# 13_Periphs.net
KiCad netlist of a schematic drawn in Altium Designer
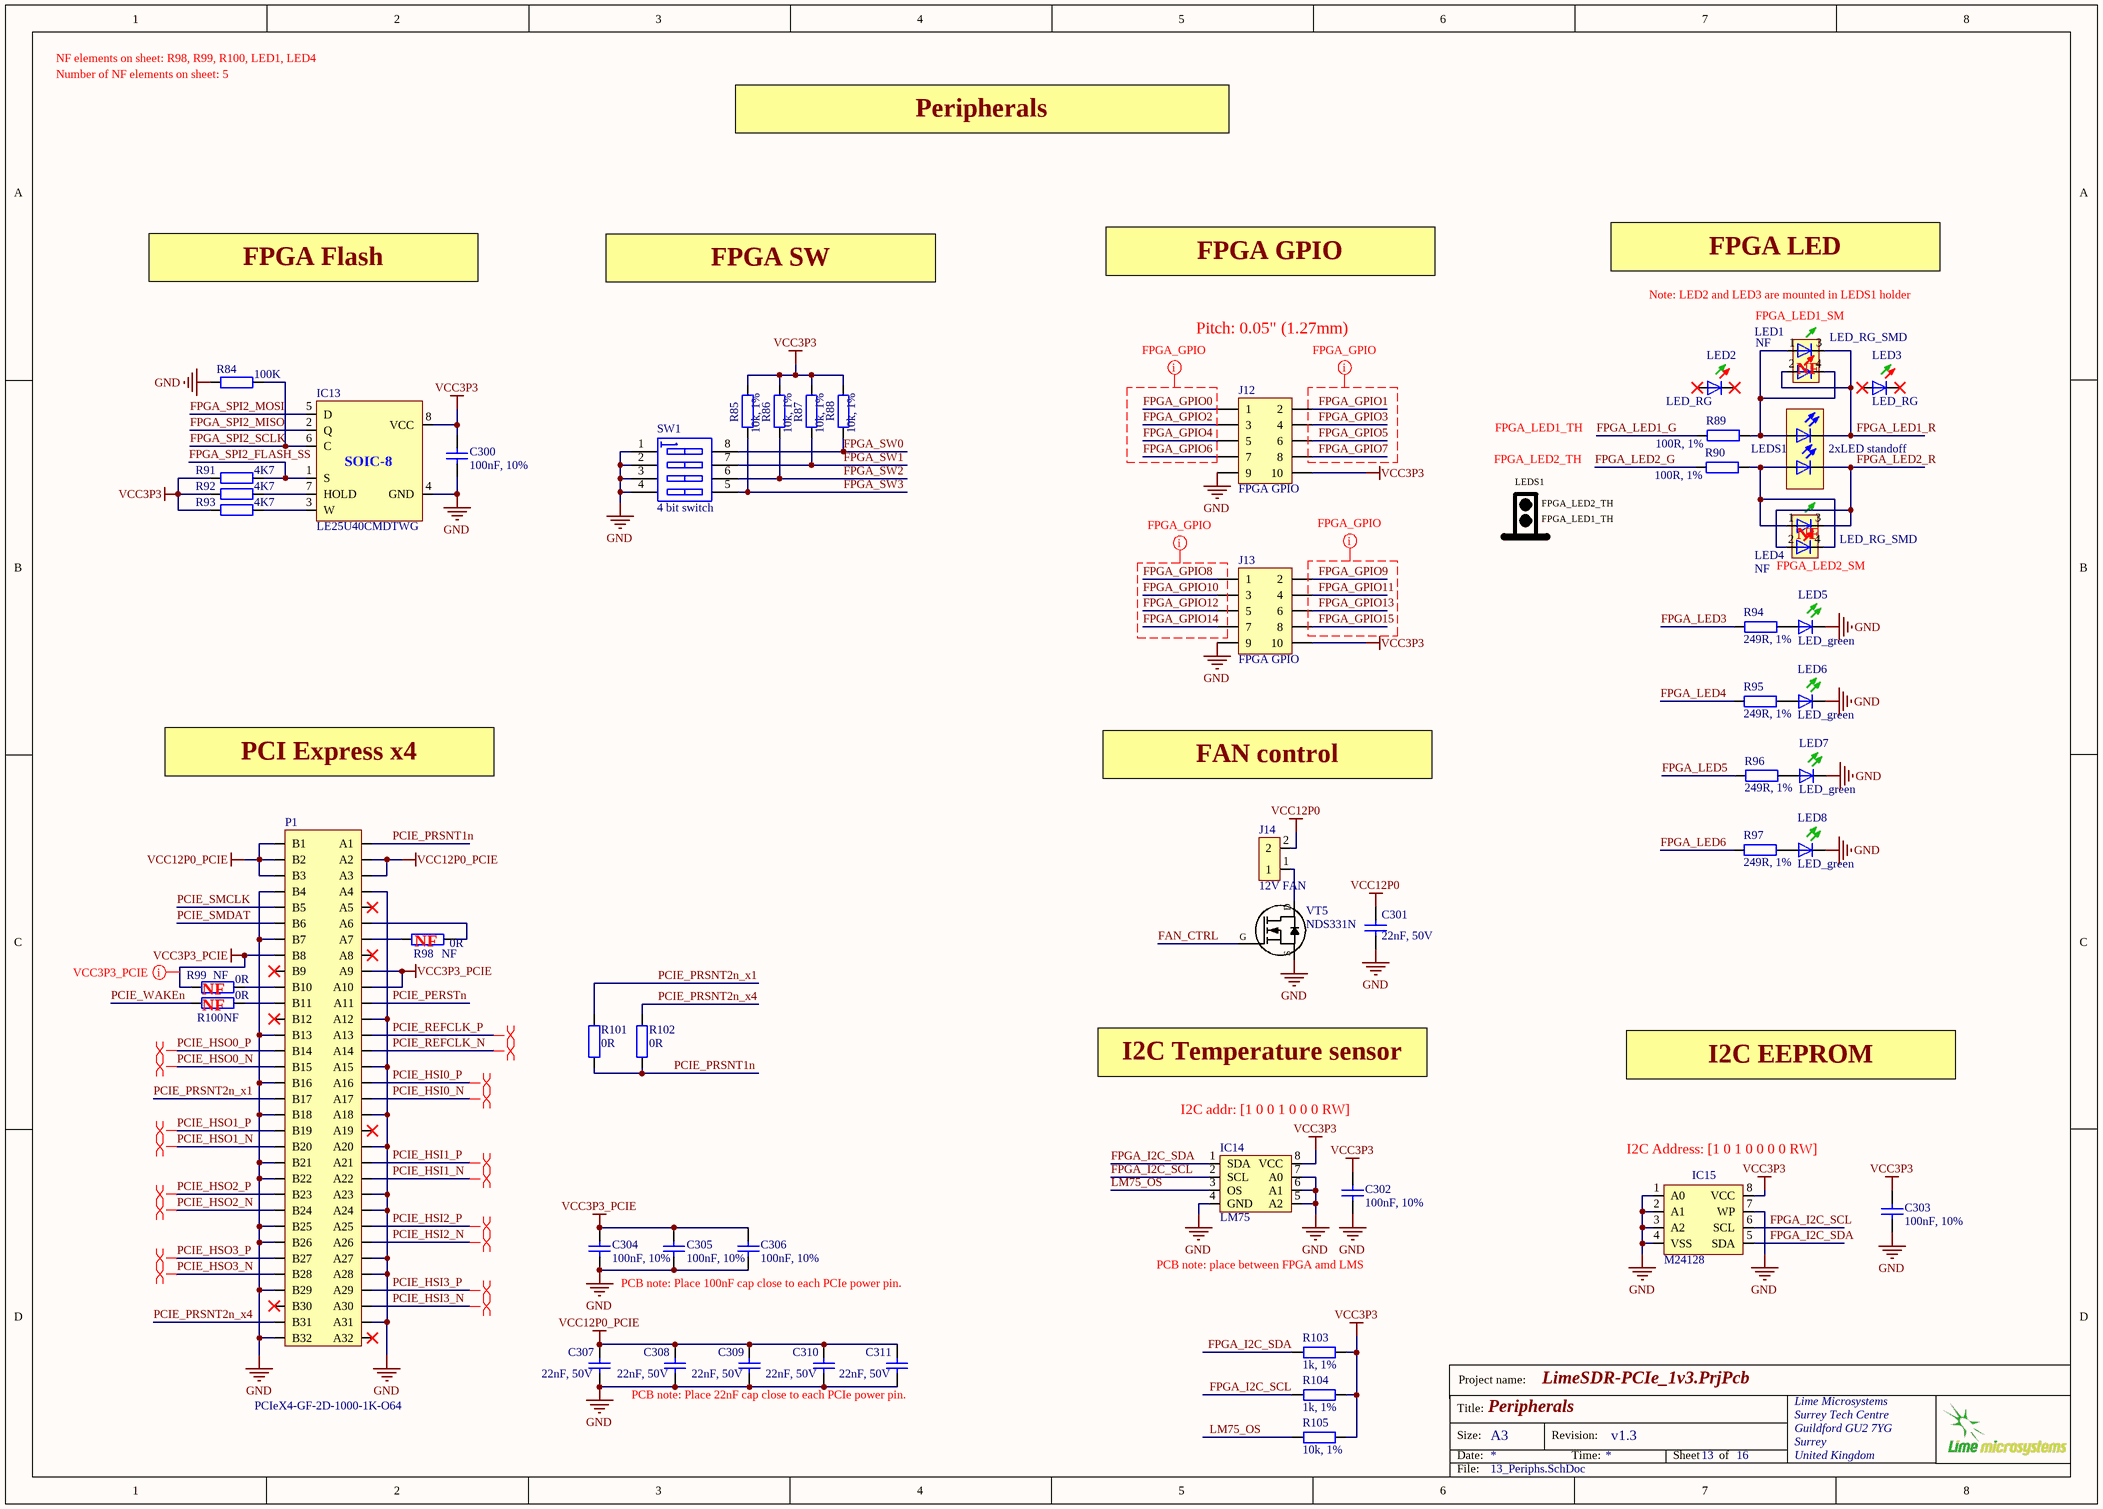
[diagram p0: 13_Periphs.SchDoc]

(export (version "E")
  (design (tool "Eeschema 10.0.6"))
  (components
    (comp (ref "C300")
      (value "100nF, 10%")
      (footprint "CAP0402")
      (fields
        (field (name "TOLERANCE") "10 %")
        (field (name "MANUFACTURER") "Murata Electronics")
        (field (name "MANUFACTURER PART NUMBER") "GRM155R71C104KA88D")
      )
      (libsource (lib "LimeFPGAboard_schLib") (part "Cap_0603"))
    )
    (comp (ref "C301")
      (value "22nF, 50V")
      (footprint "CAP0402")
      (fields (field (name "TOLERANCE") "±10%") (field (name "MANUFACTURER") "Kemet"))
      (libsource (lib "LimeMicroAltiumLib_schLib") (part "Cap_0402"))
    )
    (comp (ref "C302")
      (value "100nF, 10%")
      (footprint "CAP0402")
      (fields
        (field (name "TOLERANCE") "10 %")
        (field (name "MANUFACTURER") "Murata Electronics")
        (field (name "MANUFACTURER PART NUMBER") "GRM155R71C104KA88D")
      )
      (libsource (lib "LimeFPGAboard_schLib") (part "Cap_0603"))
    )
    (comp (ref "C303")
      (value "100nF, 10%")
      (footprint "CAP0402")
      (fields
        (field (name "TOLERANCE") "10 %")
        (field (name "MANUFACTURER") "Murata Electronics")
        (field (name "MANUFACTURER PART NUMBER") "GRM155R71C104KA88D")
      )
      (libsource (lib "LimeFPGAboard_schLib") (part "Cap_0603"))
    )
    (comp (ref "C304")
      (value "100nF, 10%")
      (footprint "CAP0402")
      (fields
        (field (name "TOLERANCE") "10 %")
        (field (name "MANUFACTURER") "Murata Electronics")
        (field (name "MANUFACTURER PART NUMBER") "GRM155R71C104KA88D")
      )
      (libsource (lib "LimeFPGAboard_schLib") (part "Cap_0603"))
    )
    (comp (ref "C305")
      (value "100nF, 10%")
      (footprint "CAP0402")
      (fields
        (field (name "TOLERANCE") "10 %")
        (field (name "MANUFACTURER") "Murata Electronics")
        (field (name "MANUFACTURER PART NUMBER") "GRM155R71C104KA88D")
      )
      (libsource (lib "LimeFPGAboard_schLib") (part "Cap_0603"))
    )
    (comp (ref "C306")
      (value "100nF, 10%")
      (footprint "CAP0402")
      (fields
        (field (name "TOLERANCE") "10 %")
        (field (name "MANUFACTURER") "Murata Electronics")
        (field (name "MANUFACTURER PART NUMBER") "GRM155R71C104KA88D")
      )
      (libsource (lib "LimeFPGAboard_schLib") (part "Cap_0603"))
    )
    (comp (ref "C307")
      (value "22nF, 50V")
      (footprint "CAP0402")
      (fields (field (name "TOLERANCE") "±10%") (field (name "MANUFACTURER") "Kemet"))
      (libsource (lib "LimeMicroAltiumLib_schLib") (part "Cap_0402"))
    )
    (comp (ref "C308")
      (value "22nF, 50V")
      (footprint "CAP0402")
      (fields (field (name "TOLERANCE") "±10%") (field (name "MANUFACTURER") "Kemet"))
      (libsource (lib "LimeMicroAltiumLib_schLib") (part "Cap_0402"))
    )
    (comp (ref "C309")
      (value "22nF, 50V")
      (footprint "CAP0402")
      (fields (field (name "TOLERANCE") "±10%") (field (name "MANUFACTURER") "Kemet"))
      (libsource (lib "LimeMicroAltiumLib_schLib") (part "Cap_0402"))
    )
    (comp (ref "C310")
      (value "22nF, 50V")
      (footprint "CAP0402")
      (fields (field (name "TOLERANCE") "±10%") (field (name "MANUFACTURER") "Kemet"))
      (libsource (lib "LimeMicroAltiumLib_schLib") (part "Cap_0402"))
    )
    (comp (ref "C311")
      (value "22nF, 50V")
      (footprint "CAP0402")
      (fields (field (name "TOLERANCE") "±10%") (field (name "MANUFACTURER") "Kemet"))
      (libsource (lib "LimeMicroAltiumLib_schLib") (part "Cap_0402"))
    )
    (comp (ref "IC13")
      (value "LE25U40CMDTWG")
      (footprint "M25P40-VMN6TPB_SO8N")
      (description "IC FLASH 4MBIT 40MHZ 8SOIC")
      (fields (field (name "MANUFACTURER") "ON Semiconductor"))
      (libsource (lib "LimeFPGAboard_schLib") (part "M25P40"))
    )
    (comp (ref "IC14")
      (value "LM75")
      (footprint "HWSON8_LM75")
      (fields
        (field (name "MANUFACTURER") "NXP Semiconductors")
        (field (name "MANUFACTURER PART NUMBER") "LM75BTP,147")
      )
      (libsource (lib "LimeMicroAltiumLib_schLib") (part "LM75"))
    )
    (comp (ref "IC15")
      (value "M24128")
      (footprint "24FC512")
      (fields (field (name "MANUFACTURER") "STMicroelectronics"))
      (libsource (lib "LimeMicroAltiumLib_schLib") (part "24FC64F"))
    )
    (comp (ref "J12")
      (value "FPGA GPIO")
      (footprint "SWD_10_pin")
      (description "Header, 5-Pin, Dual row")
      (fields (field (name "MANUFACTURER") "Harwin Inc"))
      (libsource (lib "LimeMicroAltiumLib_schLib") (part "Header 5X2_SWD"))
    )
    (comp (ref "J13")
      (value "FPGA GPIO")
      (footprint "SWD_10_pin")
      (description "Header, 5-Pin, Dual row")
      (fields (field (name "MANUFACTURER") "Harwin Inc"))
      (libsource (lib "LimeMicroAltiumLib_schLib") (part "Header 5X2_SWD"))
    )
    (comp (ref "J14")
      (value "12V FAN")
      (footprint "HDR_1x2")
      (fields (field (name "MANUFACTURER") "3M"))
      (libsource (lib "LimeFPGAboard_schLib") (part "Jumper"))
    )
    (comp (ref "LED1")
      (value "LED_RG_SMD")
      (footprint "LED-2x0603")
      (fields (field (name "MANUFACTURER") "Avago Technologies US Inc.") (field (name "ASSEMBLY INFO") "NF"))
      (libsource (lib "LimeMicroAltiumLib_schLib") (part "LED_green_red_SMD"))
    )
    (comp (ref "LED2")
      (value "LED_RG")
      (fields (field (name "MANUFACTURER") "Visual Communications Company - VCC"))
      (libsource (lib "LimeMicroAltiumLib_schLib") (part "LED_green_red"))
    )
    (comp (ref "LED3")
      (value "LED_RG")
      (fields (field (name "MANUFACTURER") "Visual Communications Company - VCC"))
      (libsource (lib "LimeMicroAltiumLib_schLib") (part "LED_green_red"))
    )
    (comp (ref "LED4")
      (value "LED_RG_SMD")
      (footprint "LED-2x0603")
      (fields (field (name "MANUFACTURER") "Avago Technologies US Inc.") (field (name "ASSEMBLY INFO") "NF"))
      (libsource (lib "LimeMicroAltiumLib_schLib") (part "LED_green_red_SMD"))
    )
    (comp (ref "LED5")
      (value "LED_green")
      (footprint "LED-0603-GREEN")
      (fields (field (name "MANUFACTURER") "Broadcom Limited"))
      (libsource (lib "LimeFPGAboard_schLib") (part "LED_green"))
    )
    (comp (ref "LED6")
      (value "LED_green")
      (footprint "LED-0603-GREEN")
      (fields (field (name "MANUFACTURER") "Broadcom Limited"))
      (libsource (lib "LimeFPGAboard_schLib") (part "LED_green"))
    )
    (comp (ref "LED7")
      (value "LED_green")
      (footprint "LED-0603-GREEN")
      (fields (field (name "MANUFACTURER") "Broadcom Limited"))
      (libsource (lib "LimeFPGAboard_schLib") (part "LED_green"))
    )
    (comp (ref "LED8")
      (value "LED_green")
      (footprint "LED-0603-GREEN")
      (fields (field (name "MANUFACTURER") "Broadcom Limited"))
      (libsource (lib "LimeFPGAboard_schLib") (part "LED_green"))
    )
    (comp (ref "LEDS1")
      (value "2xLED standoff")
      (footprint "LED_STANDOFF_H-201C")
      (fields (field (name "MANUFACTURER") "Bivar Inc."))
      (libsource (lib "LimeMicroAltiumLib_schLib") (part "LEDx2_STANDOFF"))
    )
    (comp (ref "P1")
      (value "PCIeX4-GF-2D-1000-1K-O64")
      (footprint "PCIeX4-GF-2D-1000-1K-O64")
      (libsource (lib "LimeMicroAltiumLib_schLib") (part "PCIeX4-GF-2D-1000-1K-O64"))
    )
    (comp (ref "R84")
      (value "100K")
      (footprint "RES0402")
      (fields
        (field (name "TOLERANCE") "±5%")
        (field (name "MANUFACTURER") "Panasonic Electronic Components")
      )
      (libsource (lib "LimeFPGAboard_schLib") (part "Res_0402"))
    )
    (comp (ref "R85")
      (value "10k, 1%")
      (footprint "RES0402")
      (fields (field (name "MANUFACTURER") "Yageo") (field (name "TOLERANCE") "±1%"))
      (libsource (lib "LimeMicroAltiumLib_schLib") (part "Res_0402"))
    )
    (comp (ref "R86")
      (value "10k, 1%")
      (footprint "RES0402")
      (fields (field (name "MANUFACTURER") "Yageo") (field (name "TOLERANCE") "±1%"))
      (libsource (lib "LimeMicroAltiumLib_schLib") (part "Res_0402"))
    )
    (comp (ref "R87")
      (value "10k, 1%")
      (footprint "RES0402")
      (fields (field (name "MANUFACTURER") "Yageo") (field (name "TOLERANCE") "±1%"))
      (libsource (lib "LimeMicroAltiumLib_schLib") (part "Res_0402"))
    )
    (comp (ref "R88")
      (value "10k, 1%")
      (footprint "RES0402")
      (fields (field (name "MANUFACTURER") "Yageo") (field (name "TOLERANCE") "±1%"))
      (libsource (lib "LimeMicroAltiumLib_schLib") (part "Res_0402"))
    )
    (comp (ref "R89")
      (value "100R, 1%")
      (footprint "RES0402")
      (fields (field (name "TOLERANCE") "±1%") (field (name "MANUFACTURER") "Stackpole Electronics Inc."))
      (libsource (lib "LimeMicroAltiumLib_schLib") (part "Res_0402"))
    )
    (comp (ref "R90")
      (value "100R, 1%")
      (footprint "RES0402")
      (fields (field (name "TOLERANCE") "±1%") (field (name "MANUFACTURER") "Stackpole Electronics Inc."))
      (libsource (lib "LimeMicroAltiumLib_schLib") (part "Res_0402"))
    )
    (comp (ref "R91")
      (value "4K7")
      (footprint "RES0402")
      (fields (field (name "TOLERANCE") "±5%") (field (name "MANUFACTURER") "Stackpole Electronics Inc."))
      (libsource (lib "LimeFPGAboard_schLib") (part "Res_0402"))
    )
    (comp (ref "R92")
      (value "4K7")
      (footprint "RES0402")
      (fields (field (name "TOLERANCE") "±5%") (field (name "MANUFACTURER") "Stackpole Electronics Inc."))
      (libsource (lib "LimeFPGAboard_schLib") (part "Res_0402"))
    )
    (comp (ref "R93")
      (value "4K7")
      (footprint "RES0402")
      (fields (field (name "TOLERANCE") "±5%") (field (name "MANUFACTURER") "Stackpole Electronics Inc."))
      (libsource (lib "LimeFPGAboard_schLib") (part "Res_0402"))
    )
    (comp (ref "R94")
      (value "249R, 1%")
      (footprint "RES0402")
      (fields (field (name "MANUFACTURER") "Stackpole Electronics Inc") (field (name "TOLERANCE") "±1%"))
      (libsource (lib "LimeMicroAltiumLib_schLib") (part "Res_0402"))
    )
    (comp (ref "R95")
      (value "249R, 1%")
      (footprint "RES0402")
      (fields (field (name "MANUFACTURER") "Stackpole Electronics Inc") (field (name "TOLERANCE") "±1%"))
      (libsource (lib "LimeMicroAltiumLib_schLib") (part "Res_0402"))
    )
    (comp (ref "R96")
      (value "249R, 1%")
      (footprint "RES0402")
      (fields (field (name "MANUFACTURER") "Stackpole Electronics Inc") (field (name "TOLERANCE") "±1%"))
      (libsource (lib "LimeMicroAltiumLib_schLib") (part "Res_0402"))
    )
    (comp (ref "R97")
      (value "249R, 1%")
      (footprint "RES0402")
      (fields (field (name "MANUFACTURER") "Stackpole Electronics Inc") (field (name "TOLERANCE") "±1%"))
      (libsource (lib "LimeMicroAltiumLib_schLib") (part "Res_0402"))
    )
    (comp (ref "R98")
      (value "0R")
      (footprint "RES0402")
      (fields (field (name "MANUFACTURER") "Yageo") (field (name "ASSEMBLY INFO") "NF"))
      (libsource (lib "LimeFPGAboard_schLib") (part "Res_0402"))
    )
    (comp (ref "R99")
      (value "0R")
      (footprint "RES0402")
      (fields (field (name "MANUFACTURER") "Yageo") (field (name "ASSEMBLY INFO") "NF"))
      (libsource (lib "LimeFPGAboard_schLib") (part "Res_0402"))
    )
    (comp (ref "R100")
      (value "0R")
      (footprint "RES0402")
      (fields (field (name "MANUFACTURER") "Yageo") (field (name "ASSEMBLY INFO") "NF"))
      (libsource (lib "LimeFPGAboard_schLib") (part "Res_0402"))
    )
    (comp (ref "R101")
      (value "0R")
      (footprint "RES0402")
      (fields (field (name "MANUFACTURER") "Yageo"))
      (libsource (lib "LimeFPGAboard_schLib") (part "Res_0402"))
    )
    (comp (ref "R102")
      (value "0R")
      (footprint "RES0402")
      (fields (field (name "MANUFACTURER") "Yageo"))
      (libsource (lib "LimeFPGAboard_schLib") (part "Res_0402"))
    )
    (comp (ref "R103")
      (value "1k, 1%")
      (footprint "RES0402")
      (fields (field (name "MANUFACTURER") "Stackpole Electronics Inc") (field (name "TOLERANCE") "±1%"))
      (libsource (lib "LimeMicroAltiumLib_schLib") (part "Res_0402"))
    )
    (comp (ref "R104")
      (value "1k, 1%")
      (footprint "RES0402")
      (fields (field (name "MANUFACTURER") "Stackpole Electronics Inc") (field (name "TOLERANCE") "±1%"))
      (libsource (lib "LimeMicroAltiumLib_schLib") (part "Res_0402"))
    )
    (comp (ref "R105")
      (value "10k, 1%")
      (footprint "RES0402")
      (fields (field (name "MANUFACTURER") "Yageo") (field (name "TOLERANCE") "±1%"))
      (libsource (lib "LimeMicroAltiumLib_schLib") (part "Res_0402"))
    )
    (comp (ref "SW1")
      (value "4 bit switch")
      (footprint "SW_4WAY_SMD_1P27")
      (fields (field (name "MANUFACTURER") "Omron Electronics Inc-EMC Div"))
      (libsource (lib "LimeMicroAltiumLib_schLib") (part "SW_SM_4bit"))
    )
    (comp (ref "VT5")
      (value "NDS331N")
      (footprint "SOT23-3")
      (fields (field (name "MANUFACTURER") "FAIRCHILD SEMICONDUCTOR"))
      (libsource (lib "LimeFPGAboard_schLib") (part "NDS331N"))
    )
  )
  (nets
    (net (code "1") (name "/FAN_CTRL") (class "Default")
      (node (ref "VT5") (pin "G") (pinfunction "G_G") (pintype "passive"))
    )
    (net (code "2") (name "/FPGA_GPIO0") (class "Default")
      (node (ref "J12") (pin "1") (pinfunction "1_1") (pintype "passive"))
    )
    (net (code "3") (name "/FPGA_GPIO1") (class "Default")
      (node (ref "J12") (pin "2") (pinfunction "2_2") (pintype "passive"))
    )
    (net (code "4") (name "/FPGA_GPIO2") (class "Default")
      (node (ref "J12") (pin "3") (pinfunction "3_3") (pintype "passive"))
    )
    (net (code "5") (name "/FPGA_GPIO3") (class "Default")
      (node (ref "J12") (pin "4") (pinfunction "4_4") (pintype "passive"))
    )
    (net (code "6") (name "/FPGA_GPIO4") (class "Default")
      (node (ref "J12") (pin "5") (pinfunction "5_5") (pintype "passive"))
    )
    (net (code "7") (name "/FPGA_GPIO5") (class "Default")
      (node (ref "J12") (pin "6") (pinfunction "6_6") (pintype "passive"))
    )
    (net (code "8") (name "/FPGA_GPIO6") (class "Default")
      (node (ref "J12") (pin "7") (pinfunction "7_7") (pintype "passive"))
    )
    (net (code "9") (name "/FPGA_GPIO7") (class "Default")
      (node (ref "J12") (pin "8") (pinfunction "8_8") (pintype "passive"))
    )
    (net (code "10") (name "/FPGA_GPIO8") (class "Default")
      (node (ref "J13") (pin "1") (pinfunction "1_1") (pintype "passive"))
    )
    (net (code "11") (name "/FPGA_GPIO9") (class "Default")
      (node (ref "J13") (pin "2") (pinfunction "2_2") (pintype "passive"))
    )
    (net (code "12") (name "/FPGA_GPIO10") (class "Default")
      (node (ref "J13") (pin "3") (pinfunction "3_3") (pintype "passive"))
    )
    (net (code "13") (name "/FPGA_GPIO11") (class "Default")
      (node (ref "J13") (pin "4") (pinfunction "4_4") (pintype "passive"))
    )
    (net (code "14") (name "/FPGA_GPIO12") (class "Default")
      (node (ref "J13") (pin "5") (pinfunction "5_5") (pintype "passive"))
    )
    (net (code "15") (name "/FPGA_GPIO13") (class "Default")
      (node (ref "J13") (pin "6") (pinfunction "6_6") (pintype "passive"))
    )
    (net (code "16") (name "/FPGA_GPIO14") (class "Default")
      (node (ref "J13") (pin "7") (pinfunction "7_7") (pintype "passive"))
    )
    (net (code "17") (name "/FPGA_GPIO15") (class "Default")
      (node (ref "J13") (pin "8") (pinfunction "8_8") (pintype "passive"))
    )
    (net (code "18") (name "/FPGA_I2C_SCL") (class "Default")
      (node (ref "IC14") (pin "2") (pinfunction "SCL_2") (pintype "passive"))
      (node (ref "IC15") (pin "6") (pinfunction "SCL_6") (pintype "passive"))
      (node (ref "R104") (pin "2") (pinfunction "2_2") (pintype "passive"))
    )
    (net (code "19") (name "/FPGA_I2C_SDA") (class "Default")
      (node (ref "IC14") (pin "1") (pinfunction "SDA_1") (pintype "passive"))
      (node (ref "IC15") (pin "5") (pinfunction "SDA_5") (pintype "passive"))
      (node (ref "R103") (pin "2") (pinfunction "2_2") (pintype "passive"))
    )
    (net (code "20") (name "/FPGA_LED1_G") (class "Default")
      (node (ref "R89") (pin "1") (pinfunction "1_1") (pintype "passive"))
    )
    (net (code "21") (name "/FPGA_LED1_R") (class "Default")
      (node (ref "LED1") (pin "2") (pinfunction "2_2") (pintype "power_in"))
      (node (ref "LED1") (pin "3") (pinfunction "3_3") (pintype "power_in"))
      (node (ref "LEDS1") (pin "K1") (pinfunction "C_K1") (pintype "power_in"))
    )
    (net (code "22") (name "/FPGA_LED2_G") (class "Default")
      (node (ref "R90") (pin "1") (pinfunction "1_1") (pintype "passive"))
    )
    (net (code "23") (name "/FPGA_LED2_R") (class "Default")
      (node (ref "LED4") (pin "2") (pinfunction "2_2") (pintype "power_in"))
      (node (ref "LED4") (pin "3") (pinfunction "3_3") (pintype "power_in"))
      (node (ref "LEDS1") (pin "K2") (pinfunction "C_K2") (pintype "power_in"))
    )
    (net (code "24") (name "/FPGA_LED3") (class "Default")
      (node (ref "R94") (pin "1") (pinfunction "1_1") (pintype "passive"))
    )
    (net (code "25") (name "/FPGA_LED4") (class "Default")
      (node (ref "R95") (pin "1") (pinfunction "1_1") (pintype "passive"))
    )
    (net (code "26") (name "/FPGA_LED5") (class "Default")
      (node (ref "R96") (pin "1") (pinfunction "1_1") (pintype "passive"))
    )
    (net (code "27") (name "/FPGA_LED6") (class "Default")
      (node (ref "R97") (pin "1") (pinfunction "1_1") (pintype "passive"))
    )
    (net (code "28") (name "/FPGA_SPI2_FLASH_SS") (class "Default")
      (node (ref "IC13") (pin "1") (pinfunction "S_1") (pintype "passive"))
      (node (ref "R91") (pin "2") (pinfunction "2_2") (pintype "passive"))
    )
    (net (code "29") (name "/FPGA_SPI2_MISO") (class "Default")
      (node (ref "IC13") (pin "2") (pinfunction "Q_2") (pintype "passive"))
    )
    (net (code "30") (name "/FPGA_SPI2_MOSI") (class "Default")
      (node (ref "IC13") (pin "5") (pinfunction "D_5") (pintype "passive"))
    )
    (net (code "31") (name "/FPGA_SPI2_SCLK") (class "Default")
      (node (ref "IC13") (pin "6") (pinfunction "C_6") (pintype "passive"))
      (node (ref "R84") (pin "2") (pinfunction "2_2") (pintype "passive"))
    )
    (net (code "32") (name "/FPGA_SW0") (class "Default")
      (node (ref "R88") (pin "2") (pinfunction "2_2") (pintype "passive"))
      (node (ref "SW1") (pin "8") (pinfunction "B1_8") (pintype "passive"))
    )
    (net (code "33") (name "/FPGA_SW1") (class "Default")
      (node (ref "R87") (pin "2") (pinfunction "2_2") (pintype "passive"))
      (node (ref "SW1") (pin "7") (pinfunction "B2_7") (pintype "passive"))
    )
    (net (code "34") (name "/FPGA_SW2") (class "Default")
      (node (ref "R86") (pin "2") (pinfunction "2_2") (pintype "passive"))
      (node (ref "SW1") (pin "6") (pinfunction "B3_6") (pintype "passive"))
    )
    (net (code "35") (name "/FPGA_SW3") (class "Default")
      (node (ref "R85") (pin "2") (pinfunction "2_2") (pintype "passive"))
      (node (ref "SW1") (pin "5") (pinfunction "B4_5") (pintype "passive"))
    )
    (net (code "36") (name "/LM75_OS") (class "Default")
      (node (ref "IC14") (pin "3") (pinfunction "OS_3") (pintype "passive"))
      (node (ref "R105") (pin "2") (pinfunction "2_2") (pintype "passive"))
    )
    (net (code "37") (name "/PCIE_HSI0_N") (class "Default")
      (node (ref "P1") (pin "A17") (pinfunction "A17_A17") (pintype "passive"))
    )
    (net (code "38") (name "/PCIE_HSI0_P") (class "Default")
      (node (ref "P1") (pin "A16") (pinfunction "A16_A16") (pintype "passive"))
    )
    (net (code "39") (name "/PCIE_HSI1_N") (class "Default")
      (node (ref "P1") (pin "A22") (pinfunction "A22_A22") (pintype "passive"))
    )
    (net (code "40") (name "/PCIE_HSI1_P") (class "Default")
      (node (ref "P1") (pin "A21") (pinfunction "A21_A21") (pintype "passive"))
    )
    (net (code "41") (name "/PCIE_HSI2_N") (class "Default")
      (node (ref "P1") (pin "A26") (pinfunction "A26_A26") (pintype "passive"))
    )
    (net (code "42") (name "/PCIE_HSI2_P") (class "Default")
      (node (ref "P1") (pin "A25") (pinfunction "A25_A25") (pintype "passive"))
    )
    (net (code "43") (name "/PCIE_HSI3_N") (class "Default")
      (node (ref "P1") (pin "A30") (pinfunction "A30_A30") (pintype "passive"))
    )
    (net (code "44") (name "/PCIE_HSI3_P") (class "Default")
      (node (ref "P1") (pin "A29") (pinfunction "A29_A29") (pintype "passive"))
    )
    (net (code "45") (name "/PCIE_HSO0_N") (class "Default")
      (node (ref "P1") (pin "B15") (pinfunction "B15_B15") (pintype "passive"))
    )
    (net (code "46") (name "/PCIE_HSO0_P") (class "Default")
      (node (ref "P1") (pin "B14") (pinfunction "B14_B14") (pintype "passive"))
    )
    (net (code "47") (name "/PCIE_HSO1_N") (class "Default")
      (node (ref "P1") (pin "B20") (pinfunction "B20_B20") (pintype "passive"))
    )
    (net (code "48") (name "/PCIE_HSO1_P") (class "Default")
      (node (ref "P1") (pin "B19") (pinfunction "B19_B19") (pintype "passive"))
    )
    (net (code "49") (name "/PCIE_HSO2_N") (class "Default")
      (node (ref "P1") (pin "B24") (pinfunction "B24_B24") (pintype "passive"))
    )
    (net (code "50") (name "/PCIE_HSO2_P") (class "Default")
      (node (ref "P1") (pin "B23") (pinfunction "B23_B23") (pintype "passive"))
    )
    (net (code "51") (name "/PCIE_HSO3_N") (class "Default")
      (node (ref "P1") (pin "B28") (pinfunction "B28_B28") (pintype "passive"))
    )
    (net (code "52") (name "/PCIE_HSO3_P") (class "Default")
      (node (ref "P1") (pin "B27") (pinfunction "B27_B27") (pintype "passive"))
    )
    (net (code "53") (name "/PCIE_PERSTn") (class "Default")
      (node (ref "P1") (pin "A11") (pinfunction "A11_A11") (pintype "passive"))
    )
    (net (code "54") (name "/PCIE_PRSNT1n") (class "Default")
      (node (ref "P1") (pin "A1") (pinfunction "A1_A1") (pintype "passive"))
      (node (ref "R101") (pin "1") (pinfunction "1_1") (pintype "passive"))
      (node (ref "R102") (pin "1") (pinfunction "1_1") (pintype "passive"))
    )
    (net (code "55") (name "/PCIE_PRSNT2n_x1") (class "Default")
      (node (ref "P1") (pin "B17") (pinfunction "B17_B17") (pintype "passive"))
      (node (ref "R101") (pin "2") (pinfunction "2_2") (pintype "passive"))
    )
    (net (code "56") (name "/PCIE_PRSNT2n_x4") (class "Default")
      (node (ref "P1") (pin "B31") (pinfunction "B31_B31") (pintype "passive"))
      (node (ref "R102") (pin "2") (pinfunction "2_2") (pintype "passive"))
    )
    (net (code "57") (name "/PCIE_REFCLK_N") (class "Default")
      (node (ref "P1") (pin "A14") (pinfunction "A14_A14") (pintype "passive"))
    )
    (net (code "58") (name "/PCIE_REFCLK_P") (class "Default")
      (node (ref "P1") (pin "A13") (pinfunction "A13_A13") (pintype "passive"))
    )
    (net (code "59") (name "/PCIE_SMCLK") (class "Default")
      (node (ref "P1") (pin "B5") (pinfunction "B5_B5") (pintype "passive"))
    )
    (net (code "60") (name "/PCIE_SMDAT") (class "Default")
      (node (ref "P1") (pin "B6") (pinfunction "B6_B6") (pintype "passive"))
    )
    (net (code "61") (name "/PCIE_WAKEn") (class "Default")
      (node (ref "R100") (pin "1") (pinfunction "1_1") (pintype "passive"))
    )
    (net (code "62") (name "GND") (class "Default")
      (node (ref "C300") (pin "2") (pinfunction "2_2") (pintype "passive"))
      (node (ref "C301") (pin "2") (pinfunction "2_2") (pintype "passive"))
      (node (ref "C302") (pin "2") (pinfunction "2_2") (pintype "passive"))
      (node (ref "C303") (pin "2") (pinfunction "2_2") (pintype "passive"))
      (node (ref "C304") (pin "2") (pinfunction "2_2") (pintype "passive"))
      (node (ref "C305") (pin "2") (pinfunction "2_2") (pintype "passive"))
      (node (ref "C306") (pin "2") (pinfunction "2_2") (pintype "passive"))
      (node (ref "C307") (pin "2") (pinfunction "2_2") (pintype "passive"))
      (node (ref "C308") (pin "2") (pinfunction "2_2") (pintype "passive"))
      (node (ref "C309") (pin "2") (pinfunction "2_2") (pintype "passive"))
      (node (ref "C310") (pin "2") (pinfunction "2_2") (pintype "passive"))
      (node (ref "C311") (pin "2") (pinfunction "2_2") (pintype "passive"))
      (node (ref "IC13") (pin "4") (pinfunction "GND_4") (pintype "passive"))
      (node (ref "IC14") (pin "4") (pinfunction "GND_4") (pintype "passive"))
      (node (ref "IC14") (pin "5") (pinfunction "A2_5") (pintype "passive"))
      (node (ref "IC14") (pin "6") (pinfunction "A1_6") (pintype "passive"))
      (node (ref "IC14") (pin "7") (pinfunction "A0_7") (pintype "passive"))
      (node (ref "IC15") (pin "1") (pinfunction "A0_1") (pintype "passive"))
      (node (ref "IC15") (pin "2") (pinfunction "A1_2") (pintype "passive"))
      (node (ref "IC15") (pin "3") (pinfunction "A2_3") (pintype "passive"))
      (node (ref "IC15") (pin "4") (pinfunction "VSS_4") (pintype "passive"))
      (node (ref "IC15") (pin "7") (pinfunction "WP_7") (pintype "passive"))
      (node (ref "J12") (pin "9") (pinfunction "9_9") (pintype "passive"))
      (node (ref "J13") (pin "9") (pinfunction "9_9") (pintype "passive"))
      (node (ref "LED5") (pin "K") (pinfunction "C_K") (pintype "power_in"))
      (node (ref "LED6") (pin "K") (pinfunction "C_K") (pintype "power_in"))
      (node (ref "LED7") (pin "K") (pinfunction "C_K") (pintype "power_in"))
      (node (ref "LED8") (pin "K") (pinfunction "C_K") (pintype "power_in"))
      (node (ref "P1") (pin "A12") (pinfunction "A12_A12") (pintype "passive"))
      (node (ref "P1") (pin "A15") (pinfunction "A15_A15") (pintype "passive"))
      (node (ref "P1") (pin "A18") (pinfunction "A18_A18") (pintype "passive"))
      (node (ref "P1") (pin "A20") (pinfunction "A20_A20") (pintype "passive"))
      (node (ref "P1") (pin "A23") (pinfunction "A23_A23") (pintype "passive"))
      (node (ref "P1") (pin "A24") (pinfunction "A24_A24") (pintype "passive"))
      (node (ref "P1") (pin "A27") (pinfunction "A27_A27") (pintype "passive"))
      (node (ref "P1") (pin "A28") (pinfunction "A28_A28") (pintype "passive"))
      (node (ref "P1") (pin "A31") (pinfunction "A31_A31") (pintype "passive"))
      (node (ref "P1") (pin "A4") (pinfunction "A4_A4") (pintype "passive"))
      (node (ref "P1") (pin "B13") (pinfunction "B13_B13") (pintype "passive"))
      (node (ref "P1") (pin "B16") (pinfunction "B16_B16") (pintype "passive"))
      (node (ref "P1") (pin "B18") (pinfunction "B18_B18") (pintype "passive"))
      (node (ref "P1") (pin "B21") (pinfunction "B21_B21") (pintype "passive"))
      (node (ref "P1") (pin "B22") (pinfunction "B22_B22") (pintype "passive"))
      (node (ref "P1") (pin "B25") (pinfunction "B25_B25") (pintype "passive"))
      (node (ref "P1") (pin "B26") (pinfunction "B26_B26") (pintype "passive"))
      (node (ref "P1") (pin "B29") (pinfunction "B29_B29") (pintype "passive"))
      (node (ref "P1") (pin "B32") (pinfunction "B32_B32") (pintype "passive"))
      (node (ref "P1") (pin "B4") (pinfunction "B4_B4") (pintype "passive"))
      (node (ref "P1") (pin "B7") (pinfunction "B7_B7") (pintype "passive"))
      (node (ref "R84") (pin "1") (pinfunction "1_1") (pintype "passive"))
      (node (ref "SW1") (pin "1") (pinfunction "A1_1") (pintype "passive"))
      (node (ref "SW1") (pin "2") (pinfunction "A2_2") (pintype "passive"))
      (node (ref "SW1") (pin "3") (pinfunction "A3_3") (pintype "passive"))
      (node (ref "SW1") (pin "4") (pinfunction "A4_4") (pintype "passive"))
      (node (ref "VT5") (pin "S") (pinfunction "S_S") (pintype "passive"))
    )
    (net (code "63") (name "Net-(IC13-HOLD)") (class "Default")
      (node (ref "IC13") (pin "7") (pinfunction "HOLD_7") (pintype "passive"))
      (node (ref "R92") (pin "2") (pinfunction "2_2") (pintype "passive"))
    )
    (net (code "64") (name "Net-(IC13-W)") (class "Default")
      (node (ref "IC13") (pin "3") (pinfunction "W_3") (pintype "passive"))
      (node (ref "R93") (pin "2") (pinfunction "2_2") (pintype "passive"))
    )
    (net (code "65") (name "Net-(J14-Pad1)") (class "Default")
      (node (ref "J14") (pin "1") (pinfunction "1_1") (pintype "passive"))
      (node (ref "VT5") (pin "D") (pinfunction "D_D") (pintype "passive"))
    )
    (net (code "66") (name "Net-(LED1-Pad1)") (class "Default")
      (node (ref "LED1") (pin "1") (pinfunction "1_1") (pintype "power_in"))
      (node (ref "LED1") (pin "4") (pinfunction "4_4") (pintype "power_in"))
      (node (ref "LEDS1") (pin "A1") (pinfunction "A_A1") (pintype "power_in"))
      (node (ref "R89") (pin "2") (pinfunction "2_2") (pintype "passive"))
    )
    (net (code "67") (name "Net-(LED4-Pad1)") (class "Default")
      (node (ref "LED4") (pin "1") (pinfunction "1_1") (pintype "power_in"))
      (node (ref "LED4") (pin "4") (pinfunction "4_4") (pintype "power_in"))
      (node (ref "LEDS1") (pin "A2") (pinfunction "A_A2") (pintype "power_in"))
      (node (ref "R90") (pin "2") (pinfunction "2_2") (pintype "passive"))
    )
    (net (code "68") (name "Net-(LED5-PadA)") (class "Default")
      (node (ref "LED5") (pin "A") (pinfunction "A_A") (pintype "power_in"))
      (node (ref "R94") (pin "2") (pinfunction "2_2") (pintype "passive"))
    )
    (net (code "69") (name "Net-(LED6-PadA)") (class "Default")
      (node (ref "LED6") (pin "A") (pinfunction "A_A") (pintype "power_in"))
      (node (ref "R95") (pin "2") (pinfunction "2_2") (pintype "passive"))
    )
    (net (code "70") (name "Net-(LED7-PadA)") (class "Default")
      (node (ref "LED7") (pin "A") (pinfunction "A_A") (pintype "power_in"))
      (node (ref "R96") (pin "2") (pinfunction "2_2") (pintype "passive"))
    )
    (net (code "71") (name "Net-(LED8-PadA)") (class "Default")
      (node (ref "LED8") (pin "A") (pinfunction "A_A") (pintype "power_in"))
      (node (ref "R97") (pin "2") (pinfunction "2_2") (pintype "passive"))
    )
    (net (code "72") (name "Net-(P1-PadA6)") (class "Default")
      (node (ref "P1") (pin "A6") (pinfunction "A6_A6") (pintype "passive"))
      (node (ref "R98") (pin "2") (pinfunction "2_2") (pintype "passive"))
    )
    (net (code "73") (name "Net-(P1-PadA7)") (class "Default")
      (node (ref "P1") (pin "A7") (pinfunction "A7_A7") (pintype "passive"))
      (node (ref "R98") (pin "1") (pinfunction "1_1") (pintype "passive"))
    )
    (net (code "74") (name "Net-(P1-PadB10)") (class "Default")
      (node (ref "P1") (pin "B10") (pinfunction "B10_B10") (pintype "passive"))
      (node (ref "R99") (pin "2") (pinfunction "2_2") (pintype "passive"))
    )
    (net (code "75") (name "Net-(P1-PadB11)") (class "Default")
      (node (ref "P1") (pin "B11") (pinfunction "B11_B11") (pintype "passive"))
      (node (ref "R100") (pin "2") (pinfunction "2_2") (pintype "passive"))
    )
    (net (code "76") (name "VCC3P3") (class "Default")
      (node (ref "C300") (pin "1") (pinfunction "1_1") (pintype "passive"))
      (node (ref "C302") (pin "1") (pinfunction "1_1") (pintype "passive"))
      (node (ref "C303") (pin "1") (pinfunction "1_1") (pintype "passive"))
      (node (ref "IC13") (pin "8") (pinfunction "VCC_8") (pintype "passive"))
      (node (ref "IC14") (pin "8") (pinfunction "VCC_8") (pintype "passive"))
      (node (ref "IC15") (pin "8") (pinfunction "VCC_8") (pintype "passive"))
      (node (ref "J12") (pin "10") (pinfunction "10_10") (pintype "passive"))
      (node (ref "J13") (pin "10") (pinfunction "10_10") (pintype "passive"))
      (node (ref "R103") (pin "1") (pinfunction "1_1") (pintype "passive"))
      (node (ref "R104") (pin "1") (pinfunction "1_1") (pintype "passive"))
      (node (ref "R105") (pin "1") (pinfunction "1_1") (pintype "passive"))
      (node (ref "R85") (pin "1") (pinfunction "1_1") (pintype "passive"))
      (node (ref "R86") (pin "1") (pinfunction "1_1") (pintype "passive"))
      (node (ref "R87") (pin "1") (pinfunction "1_1") (pintype "passive"))
      (node (ref "R88") (pin "1") (pinfunction "1_1") (pintype "passive"))
      (node (ref "R91") (pin "1") (pinfunction "1_1") (pintype "passive"))
      (node (ref "R92") (pin "1") (pinfunction "1_1") (pintype "passive"))
      (node (ref "R93") (pin "1") (pinfunction "1_1") (pintype "passive"))
    )
    (net (code "77") (name "VCC3P3_PCIE") (class "Default")
      (node (ref "C304") (pin "1") (pinfunction "1_1") (pintype "passive"))
      (node (ref "C305") (pin "1") (pinfunction "1_1") (pintype "passive"))
      (node (ref "C306") (pin "1") (pinfunction "1_1") (pintype "passive"))
      (node (ref "P1") (pin "A10") (pinfunction "A10_A10") (pintype "passive"))
      (node (ref "P1") (pin "A9") (pinfunction "A9_A9") (pintype "passive"))
      (node (ref "P1") (pin "B8") (pinfunction "B8_B8") (pintype "passive"))
      (node (ref "R99") (pin "1") (pinfunction "1_1") (pintype "passive"))
    )
    (net (code "78") (name "VCC12P0") (class "Default")
      (node (ref "C301") (pin "1") (pinfunction "1_1") (pintype "passive"))
      (node (ref "J14") (pin "2") (pinfunction "2_2") (pintype "passive"))
    )
    (net (code "79") (name "VCC12P0_PCIE") (class "Default")
      (node (ref "C307") (pin "1") (pinfunction "1_1") (pintype "passive"))
      (node (ref "C308") (pin "1") (pinfunction "1_1") (pintype "passive"))
      (node (ref "C309") (pin "1") (pinfunction "1_1") (pintype "passive"))
      (node (ref "C310") (pin "1") (pinfunction "1_1") (pintype "passive"))
      (node (ref "C311") (pin "1") (pinfunction "1_1") (pintype "passive"))
      (node (ref "P1") (pin "A2") (pinfunction "A2_A2") (pintype "passive"))
      (node (ref "P1") (pin "A3") (pinfunction "A3_A3") (pintype "passive"))
      (node (ref "P1") (pin "B1") (pinfunction "B1_B1") (pintype "passive"))
      (node (ref "P1") (pin "B2") (pinfunction "B2_B2") (pintype "passive"))
      (node (ref "P1") (pin "B3") (pinfunction "B3_B3") (pintype "passive"))
    )
    (net (code "80") (name "unconnected-(LED2-C-PadK)") (class "Default")
      (node (ref "LED2") (pin "K") (pinfunction "C_K") (pintype "power_in+no_connect"))
    )
    (net (code "81") (name "unconnected-(LED2-PadA)") (class "Default")
      (node (ref "LED2") (pin "A") (pinfunction "A_A") (pintype "power_in+no_connect"))
    )
    (net (code "82") (name "unconnected-(LED3-C-PadK)") (class "Default")
      (node (ref "LED3") (pin "K") (pinfunction "C_K") (pintype "power_in+no_connect"))
    )
    (net (code "83") (name "unconnected-(LED3-PadA)") (class "Default")
      (node (ref "LED3") (pin "A") (pinfunction "A_A") (pintype "power_in+no_connect"))
    )
    (net (code "84") (name "unconnected-(P1-PadA5)") (class "Default")
      (node (ref "P1") (pin "A5") (pinfunction "A5_A5") (pintype "passive+no_connect"))
    )
    (net (code "85") (name "unconnected-(P1-PadA8)") (class "Default")
      (node (ref "P1") (pin "A8") (pinfunction "A8_A8") (pintype "passive+no_connect"))
    )
    (net (code "86") (name "unconnected-(P1-PadA19)") (class "Default")
      (node (ref "P1") (pin "A19") (pinfunction "A19_A19") (pintype "passive+no_connect"))
    )
    (net (code "87") (name "unconnected-(P1-PadA32)") (class "Default")
      (node (ref "P1") (pin "A32") (pinfunction "A32_A32") (pintype "passive+no_connect"))
    )
    (net (code "88") (name "unconnected-(P1-PadB9)") (class "Default")
      (node (ref "P1") (pin "B9") (pinfunction "B9_B9") (pintype "passive+no_connect"))
    )
    (net (code "89") (name "unconnected-(P1-PadB12)") (class "Default")
      (node (ref "P1") (pin "B12") (pinfunction "B12_B12") (pintype "passive+no_connect"))
    )
    (net (code "90") (name "unconnected-(P1-PadB30)") (class "Default")
      (node (ref "P1") (pin "B30") (pinfunction "B30_B30") (pintype "passive+no_connect"))
    )
  )
)
